# Power.net
KiCad netlist of a schematic drawn in Altium Designer
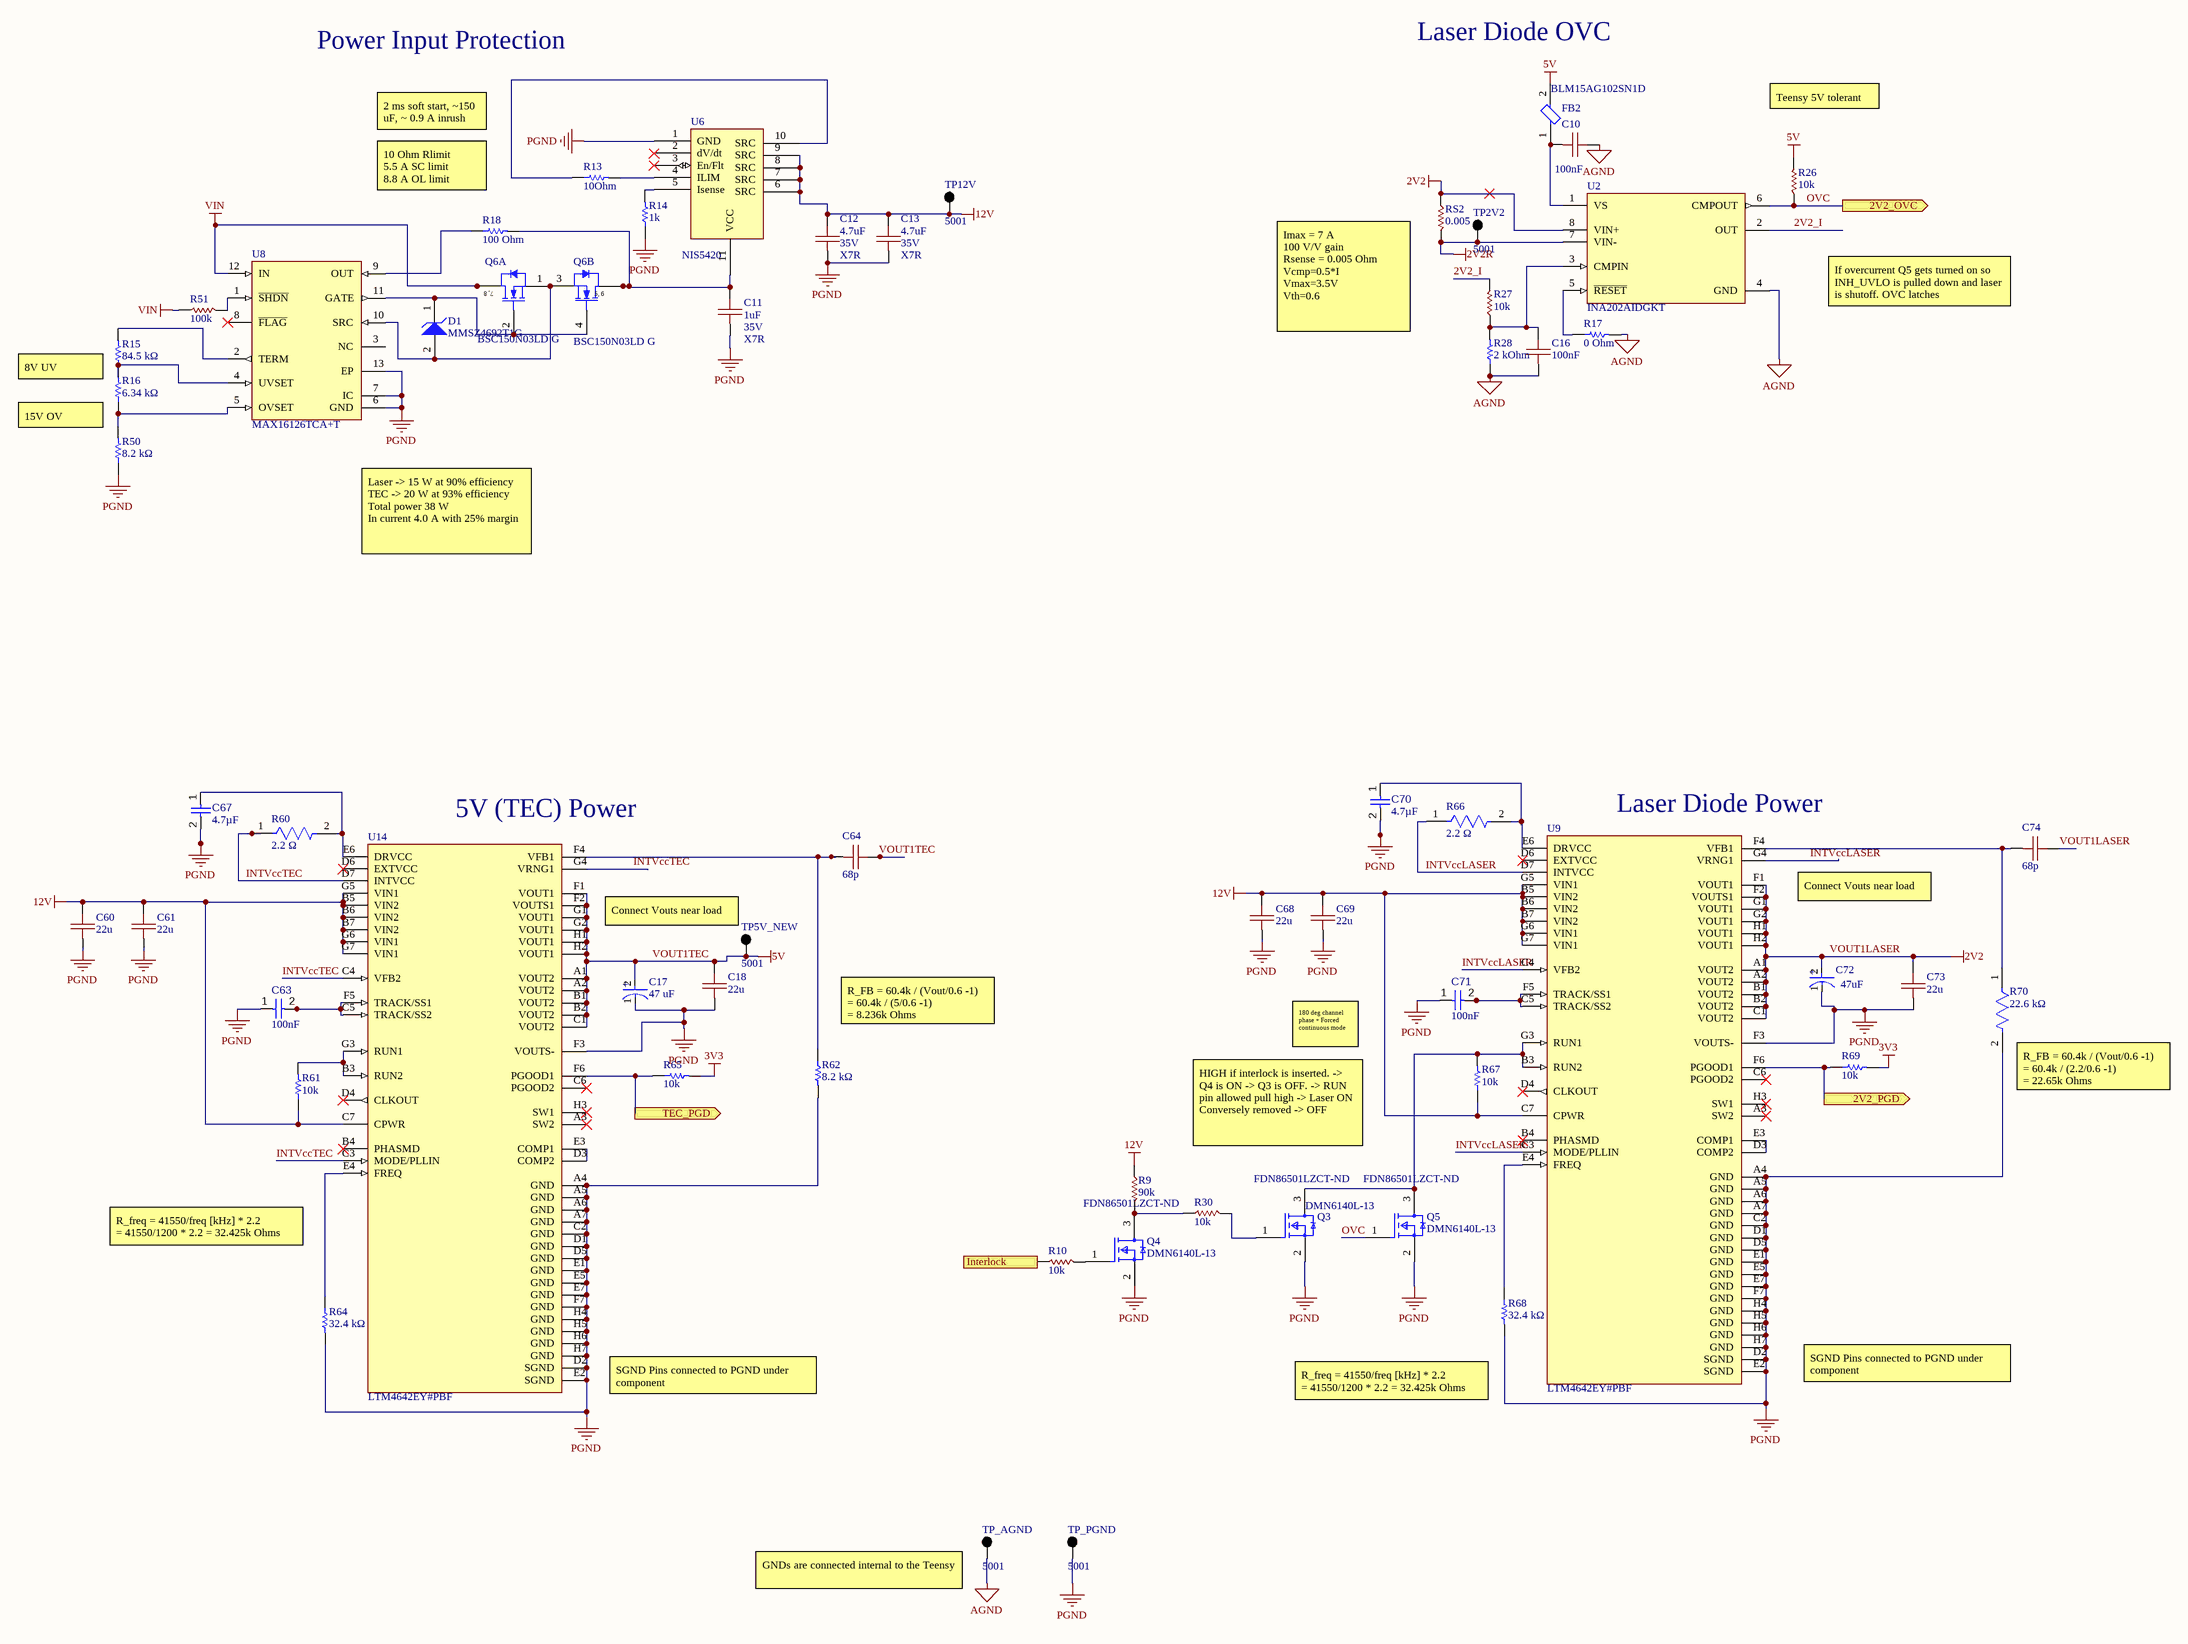
[diagram p0: Power.SchDoc]

(export (version "E")
  (design (tool "Eeschema 10.0.6"))
  (components
    (comp (ref "C10")
      (value "100nF")
      (footprint "0603 B")
      (description "603 Capacitor")
      (libsource (lib "PSSL3") (part "CAP 0603"))
    )
    (comp (ref "C11")
      (value "1uF")
      (footprint "0805 B")
      (description "805 Capacitor")
      (fields (field (name "VOLTAGE") "35V") (field (name "TYPE") "X7R"))
      (libsource (lib "PSSL3") (part "CAP 0805"))
    )
    (comp (ref "C12")
      (value "4.7uF")
      (footprint "0805 B")
      (description "805 Capacitor")
      (fields (field (name "VOLTAGE") "35V") (field (name "TYPE") "X7R"))
      (libsource (lib "PSSL3") (part "CAP 0805"))
    )
    (comp (ref "C13")
      (value "4.7uF")
      (footprint "0805 B")
      (description "805 Capacitor")
      (fields (field (name "VOLTAGE") "35V") (field (name "TYPE") "X7R"))
      (libsource (lib "PSSL3") (part "CAP 0805"))
    )
    (comp (ref "C16")
      (value "100nF")
      (footprint "0603 B")
      (description "603 Capacitor")
      (libsource (lib "PSSL3") (part "CAP 0603"))
    )
    (comp (ref "C17")
      (value "47 uF")
      (footprint "FP-T491D476K025AT-MFG")
      (description "CAP TANT 47UF 10% 25V 2917")
      (fields (field (name "VOLTAGE") "25V") (field (name "TOLERANCE") "10%"))
      (libsource (lib "Altium Content Vault") (part "203bc49f2ac43e59fd269a8c329ed05"))
    )
    (comp (ref "C18")
      (value "22u")
      (footprint "1210")
      (description "1210 Capacitor")
      (libsource (lib "PSSL3") (part "CAP 1210"))
    )
    (comp (ref "C60")
      (value "22u")
      (footprint "1210")
      (description "1210 Capacitor")
      (libsource (lib "PSSL3") (part "CAP 1210"))
    )
    (comp (ref "C61")
      (value "22u")
      (footprint "1210")
      (description "1210 Capacitor")
      (libsource (lib "PSSL3") (part "CAP 1210"))
    )
    (comp (ref "C63")
      (value "100nF")
      (footprint "CAPC1005X56X25LL10T15")
      (description "Chip Capacitor, 0.1 uF, +/- 5%, 16 V, 0402 (1005 Metric)")
      (fields (field (name "TOLERANCE") "5%") (field (name "Comment") "Capacitor 0.1 uF +/- 5% 16 V 0402"))
      (libsource (lib "MIT") (part "CAP-NP-2"))
    )
    (comp (ref "C64")
      (value "68p")
      (footprint "0805 B")
      (description "805 Capacitor")
      (libsource (lib "PSSL3") (part "CAP 0805"))
    )
    (comp (ref "C67")
      (value "4.7µF")
      (footprint "CAPC0805(2012)145_L")
      (description "Chip Capacitor, 4.7µF +/-40%, 25V, 0805, Thickness 1.45 mm")
      (fields (field (name "TOLERANCE") "20%") (field (name "Comment") "Capacitor 4.7µF +/-40% 25V 0805"))
      (libsource (lib "MIT") (part "CAP-NP-2"))
    )
    (comp (ref "C68")
      (value "22u")
      (footprint "1210")
      (description "1210 Capacitor")
      (libsource (lib "PSSL3") (part "CAP 1210"))
    )
    (comp (ref "C69")
      (value "22u")
      (footprint "1210")
      (description "1210 Capacitor")
      (libsource (lib "PSSL3") (part "CAP 1210"))
    )
    (comp (ref "C70")
      (value "4.7µF")
      (footprint "CAPC0805(2012)145_L")
      (description "Chip Capacitor, 4.7µF +/-40%, 25V, 0805, Thickness 1.45 mm")
      (fields (field (name "TOLERANCE") "20%") (field (name "Comment") "Capacitor 4.7µF +/-40% 25V 0805"))
      (libsource (lib "MIT") (part "CAP-NP-2"))
    )
    (comp (ref "C71")
      (value "100nF")
      (footprint "CAPC1005X56X25LL10T15")
      (description "Chip Capacitor, 0.1 uF, +/- 5%, 16 V, 0402 (1005 Metric)")
      (fields (field (name "TOLERANCE") "5%") (field (name "Comment") "Capacitor 0.1 uF +/- 5% 16 V 0402"))
      (libsource (lib "MIT") (part "CAP-NP-2"))
    )
    (comp (ref "C72")
      (value "47 uF")
      (footprint "FP-T491D476K025AT-MFG")
      (description "CAP TANT 47UF 10% 25V 2917")
      (fields
        (field (name "VOLTAGE") "25V")
        (field (name "CAPACITANCE") "47uF")
        (field (name "TOLERANCE") "10%")
      )
      (libsource (lib "Altium Content Vault") (part "203bc49f2ac43e59fd269a8c329ed05"))
    )
    (comp (ref "C73")
      (value "22u")
      (footprint "1210")
      (description "1210 Capacitor")
      (libsource (lib "PSSL3") (part "CAP 1210"))
    )
    (comp (ref "C74")
      (value "68p")
      (footprint "0805 B")
      (description "805 Capacitor")
      (libsource (lib "PSSL3") (part "CAP 0805"))
    )
    (comp (ref "D1")
      (value "MMSZ4692T1G")
      (footprint "ONSC-SOD-123-2-425-04_V")
      (description "Zener Voltage Regulator, 500 mW, 2-Pin SOD-123, Pb-Free, Tape and Reel")
      (fields (field (name "MANUFACTURER") "On Semiconductor"))
      (libsource (lib "Altium Content Vault") (part "ONSC-K1A2-2"))
    )
    (comp (ref "FB2")
      (value "BLM15AG102SN1D")
      (footprint "FP-BLM15-MFG")
      (description "FERRITE BEAD 1 KOHM 0402 1LN")
      (fields
        (field (name "OCTOPART") "https://octopart.com/blm15ag102sn1d-murata-368316")
        (field (name "TOLERANCE") "25%")
      )
      (libsource (lib "Altium Content Vault") (part "5f30dd21d616792df468990f7003faa"))
    )
    (comp (ref "Q3")
      (value "DMN6140L-13")
      (footprint "FP-SOT23-MFG")
      (description "MOSFET N-CH 60V 1.6A SOT23")
      (fields
        (field (name "OCTOPART") "https://octopart.com/dmn6140l-13-diodes+inc.-38898616")
        (field (name "MANUFACTURER") "Diodes Inc.")
        (field (name "SUPPLIER PART NUMBER 2") "FDN86501LZCT-ND")
      )
      (libsource (lib "Altium Content Vault") (part "0a9ea7c96deaaede766a5b531c28de0"))
    )
    (comp (ref "Q4")
      (value "DMN6140L-13")
      (footprint "FP-SOT23-MFG")
      (description "MOSFET N-CH 60V 1.6A SOT23")
      (fields
        (field (name "OCTOPART") "https://octopart.com/dmn6140l-13-diodes+inc.-38898616")
        (field (name "MANUFACTURER") "Diodes Inc.")
        (field (name "SUPPLIER PART NUMBER 2") "FDN86501LZCT-ND")
      )
      (libsource (lib "Altium Content Vault") (part "0a9ea7c96deaaede766a5b531c28de0"))
    )
    (comp (ref "Q5")
      (value "DMN6140L-13")
      (footprint "FP-SOT23-MFG")
      (description "MOSFET N-CH 60V 1.6A SOT23")
      (fields
        (field (name "OCTOPART") "https://octopart.com/dmn6140l-13-diodes+inc.-38898616")
        (field (name "MANUFACTURER") "Diodes Inc.")
        (field (name "SUPPLIER PART NUMBER 2") "FDN86501LZCT-ND")
      )
      (libsource (lib "Altium Content Vault") (part "0a9ea7c96deaaede766a5b531c28de0"))
    )
    (comp (ref "Q6")
      (value "BSC150N03LD G")
      (footprint "INF-PG-TDSON-8-4_V")
      (fields (field (name "MANUFACTURER") "Infineon"))
      (libsource (lib "Altium Content Vault") (part "INF-MOS-BSXXX-8"))
    )
    (comp (ref "R9")
      (value "90k")
      (footprint "0603")
      (description "603 Resistor")
      (libsource (lib "PSSL3") (part "RES 0603"))
    )
    (comp (ref "R10")
      (value "10k")
      (footprint "0603")
      (description "603 Resistor")
      (libsource (lib "PSSL3") (part "RES 0603"))
    )
    (comp (ref "R13")
      (value "10Ohm")
      (footprint "RESC1608X55X25NL10T15")
      (description "Chip Resistor, 10 Ohm, +/- 1%, 0.1 W, -55 to 155 degC, 0603 (1608 Metric), RoHS, Tape and Reel")
      (fields (field (name "MANUFACTURER") "Yageo"))
      (libsource (lib "Altium Content Vault") (part "RES-2"))
    )
    (comp (ref "R14")
      (value "1k")
      (footprint "RESC1608X55X30LL20T20")
      (fields (field (name "MANUFACTURER") "Panasonic") (field (name "PART NUMBER") "ERA3AEB102V"))
      (libsource (lib "Altium Content Vault") (part "RES"))
    )
    (comp (ref "R15")
      (value "84.5 kΩ")
      (footprint "RESC1609X50X30NL10T20")
      (fields (field (name "MANUFACTURER") "Vishay Dale") (field (name "PART NUMBER") "CRCW060384K5FKEA"))
      (libsource (lib "Altium Content Vault") (part "RES"))
    )
    (comp (ref "R16")
      (value "6.34 kΩ")
      (footprint "RESC1608X55X30NL15T15")
      (fields (field (name "PART NUMBER") "ERJ-3EKF6341V") (field (name "MANUFACTURER") "Panasonic"))
      (libsource (lib "Altium Content Vault") (part "RES"))
    )
    (comp (ref "R17")
      (value "0 Ohm")
      (footprint "RESC1608X55X25ML10T15")
      (description "Chip Resistor, 0 Ohm, +/- 5%, 0.1 W, -55 to 155 degC, 0603 (1608 Metric), RoHS, Tape and Reel")
      (fields (field (name "TOLERANCE") "5%") (field (name "MANUFACTURER") "Yageo"))
      (libsource (lib "Altium Content Vault") (part "RES-2"))
    )
    (comp (ref "R18")
      (value "100 Ohm")
      (footprint "RESC1608X55X30LL15T15")
      (fields (field (name "MANUFACTURER") "Panasonic") (field (name "PART NUMBER") "ERJ-3EKF1000V"))
      (libsource (lib "Altium Content Vault") (part "RES"))
    )
    (comp (ref "R26")
      (value "10k")
      (footprint "0603")
      (description "603 Resistor")
      (libsource (lib "PSSL3") (part "RES 0603"))
    )
    (comp (ref "R27")
      (value "10k")
      (footprint "0805")
      (description "805 Resistor")
      (libsource (lib "PSSL3") (part "RES 0805"))
    )
    (comp (ref "R28")
      (value "2 kOhm")
      (footprint "RESC1608X55X30ML15T15")
      (fields (field (name "PART NUMBER") "ERJ-3EKF2001V") (field (name "MANUFACTURER") "Panasonic"))
      (libsource (lib "Altium Content Vault") (part "RES"))
    )
    (comp (ref "R30")
      (value "10k")
      (footprint "0603")
      (description "603 Resistor")
      (libsource (lib "PSSL3") (part "RES 0603"))
    )
    (comp (ref "R50")
      (value "8.2 kΩ")
      (footprint "RESC1609X50X30NL10T20")
      (fields (field (name "PART NUMBER") "CRCW06038K20FKEA") (field (name "MANUFACTURER") "Vishay Dale"))
      (libsource (lib "Altium Content Vault") (part "RES"))
    )
    (comp (ref "R51")
      (value "100k")
      (footprint "0603")
      (description "603 Resistor")
      (libsource (lib "PSSL3") (part "RES 0603"))
    )
    (comp (ref "R60")
      (value "2.2 Ω")
      (footprint "FP-CRCW0603-HPe3-IPC_A")
      (description "RES Thick Film, 2.2Ω, 1%, 0.33W, 100ppm/°C, 0603")
      (fields (field (name "TOLERANCE") "1%"))
      (libsource (lib "Altium Content Vault") (part "1029c3af85768c4190bb7ad29bc67b5"))
    )
    (comp (ref "R61")
      (value "10k")
      (footprint "RESC1608X55X30LL20T20")
      (fields (field (name "MANUFACTURER") "Panasonic") (field (name "PART NUMBER") "ERA3AEB102V"))
      (libsource (lib "Altium Content Vault") (part "RES"))
    )
    (comp (ref "R62")
      (value "8.2 kΩ")
      (footprint "RESC1609X50X30ML10T20")
      (fields (field (name "PART NUMBER") "CRCW06038K20FKEA") (field (name "MANUFACTURER") "Vishay Dale"))
      (libsource (lib "Altium Content Vault") (part "RES"))
    )
    (comp (ref "R64")
      (value "32.4 kΩ")
      (footprint "RESC1609X50X30LL10T20")
      (fields (field (name "MANUFACTURER") "Vishay Dale") (field (name "PART NUMBER") "CRCW060332K4FKEA"))
      (libsource (lib "Altium Content Vault") (part "RES"))
    )
    (comp (ref "R65")
      (value "10k")
      (footprint "RESC1608X55X30LL20T20")
      (fields (field (name "MANUFACTURER") "Panasonic") (field (name "PART NUMBER") "ERA3AEB102V"))
      (libsource (lib "Altium Content Vault") (part "RES"))
    )
    (comp (ref "R66")
      (value "2.2 Ω")
      (footprint "FP-CRCW0603-HPe3-IPC_A")
      (description "RES Thick Film, 2.2Ω, 1%, 0.33W, 100ppm/°C, 0603")
      (fields (field (name "TOLERANCE") "1%"))
      (libsource (lib "Altium Content Vault") (part "1029c3af85768c4190bb7ad29bc67b5"))
    )
    (comp (ref "R67")
      (value "10k")
      (footprint "RESC1608X55X30LL20T20")
      (fields (field (name "MANUFACTURER") "Panasonic") (field (name "PART NUMBER") "ERA3AEB102V"))
      (libsource (lib "Altium Content Vault") (part "RES"))
    )
    (comp (ref "R68")
      (value "32.4 kΩ")
      (footprint "RESC1609X50X30LL10T20")
      (fields (field (name "MANUFACTURER") "Vishay Dale") (field (name "PART NUMBER") "CRCW060332K4FKEA"))
      (libsource (lib "Altium Content Vault") (part "RES"))
    )
    (comp (ref "R69")
      (value "10k")
      (footprint "RESC1608X55X30LL20T20")
      (fields (field (name "MANUFACTURER") "Panasonic") (field (name "PART NUMBER") "ERA3AEB102V"))
      (libsource (lib "Altium Content Vault") (part "RES"))
    )
    (comp (ref "R70")
      (value "22.6 kΩ")
      (footprint "FP-CRCW0402-e3-IPC_C")
      (description "RES Thick Film, 22.6kΩ, 1%, 0.063W, 100ppm/°C, 0402")
      (fields (field (name "TOLERANCE") "1%"))
      (libsource (lib "Altium Content Vault") (part "1029c3af85768c4190bb7ad29bc67b5"))
    )
    (comp (ref "RS2")
      (value "0.005")
      (footprint "1206")
      (description "1206 Resistor")
      (libsource (lib "PSSL3") (part "RES 1206"))
    )
    (comp (ref "TP2V2")
      (value "5001")
      (footprint "KSTN-5001")
      (description "Test Point, Black, 1-Pin THD, RoHS, Bulk")
      (fields (field (name "MANUFACTURER") "Keystone"))
      (libsource (lib "Altium Content Vault") (part "KSTN-TP-5001"))
    )
    (comp (ref "TP5V_NEW")
      (value "5001")
      (footprint "KSTN-5001")
      (description "Test Point, Black, 1-Pin THD, RoHS, Bulk")
      (fields (field (name "MANUFACTURER") "Keystone"))
      (libsource (lib "Altium Content Vault") (part "KSTN-TP-5001"))
    )
    (comp (ref "TP12V")
      (value "5001")
      (footprint "KSTN-5001")
      (description "Test Point, Black, 1-Pin THD, RoHS, Bulk")
      (fields (field (name "MANUFACTURER") "Keystone"))
      (libsource (lib "Altium Content Vault") (part "KSTN-TP-5001"))
    )
    (comp (ref "TP_AGND")
      (value "5001")
      (footprint "KSTN-5001")
      (description "Test Point, Black, 1-Pin THD, RoHS, Bulk")
      (fields (field (name "MANUFACTURER") "Keystone"))
      (libsource (lib "Altium Content Vault") (part "KSTN-TP-5001"))
    )
    (comp (ref "TP_PGND")
      (value "5001")
      (footprint "KSTN-5001")
      (description "Test Point, Black, 1-Pin THD, RoHS, Bulk")
      (fields (field (name "MANUFACTURER") "Keystone"))
      (libsource (lib "Altium Content Vault") (part "KSTN-TP-5001"))
    )
    (comp (ref "U2")
      (value "INA202AIDGKT")
      (footprint "FP-DGK0008A-IPC_A")
      (description "IC CURRENT MONITOR 3.5% 8VSSOP")
      (libsource (lib "Altium Content Vault") (part "ae9e9adbe4fde50626c0decd0408001"))
    )
    (comp (ref "U6")
      (value "NIS5420")
      (footprint "SON50P300X10_HS-11N")
      (libsource (lib "BeaconBoard") (part "NIS5420"))
    )
    (comp (ref "U8")
      (value "MAX16126TCA+T")
      (footprint "T1233+4_N")
      (libsource (lib "Altium Content Vault") (part "MAX-MAX16126-SQ13"))
    )
    (comp (ref "U9")
      (value "LTM4642EY#PBF")
      (footprint "FP-BGA-56-05-08-1961-MFG")
      (description "DC DC CNVRTR 0.6-5.5V 0.6-5.5V")
      (libsource (lib "Altium Content Vault") (part "2369228fab616cff492f64a44cde082"))
    )
    (comp (ref "U14")
      (value "LTM4642EY#PBF")
      (footprint "FP-BGA-56-05-08-1961-MFG")
      (description "DC DC CNVRTR 0.6-5.5V 0.6-5.5V")
      (libsource (lib "Altium Content Vault") (part "2369228fab616cff492f64a44cde082"))
    )
  )
  (nets
    (net (code "1") (name "/2V2_I") (class "Default")
      (node (ref "R27") (pin "1") (pintype "passive"))
      (node (ref "U2") (pin "2") (pinfunction "OUT_2") (pintype "passive"))
    )
    (net (code "2") (name "/2V2_PGD") (class "Default")
      (node (ref "R69") (pin "1") (pinfunction "1_1") (pintype "passive"))
      (node (ref "U9") (pin "F6") (pinfunction "PGOOD1_F6") (pintype "open_collector"))
    )
    (net (code "3") (name "/INTVccLASER") (class "Default")
      (node (ref "R66") (pin "1") (pinfunction "1_1") (pintype "passive"))
      (node (ref "U9") (pin "C3") (pinfunction "MODE/PLLIN_C3") (pintype "input"))
      (node (ref "U9") (pin "C4") (pinfunction "VFB2_C4") (pintype "input"))
      (node (ref "U9") (pin "D7") (pinfunction "INTVCC_D7") (pintype "power_in"))
      (node (ref "U9") (pin "G4") (pinfunction "VRNG1_G4") (pintype "power_in"))
    )
    (net (code "4") (name "/INTVccTEC") (class "Default")
      (node (ref "R60") (pin "1") (pinfunction "1_1") (pintype "passive"))
      (node (ref "U14") (pin "C3") (pinfunction "MODE/PLLIN_C3") (pintype "input"))
      (node (ref "U14") (pin "C4") (pinfunction "VFB2_C4") (pintype "input"))
      (node (ref "U14") (pin "D7") (pinfunction "INTVCC_D7") (pintype "power_in"))
      (node (ref "U14") (pin "G4") (pinfunction "VRNG1_G4") (pintype "power_in"))
    )
    (net (code "5") (name "/Interlock") (class "Default") (node (ref "R10") (pin "2") (pintype "passive")))
    (net (code "6") (name "/OVC") (class "Default")
      (node (ref "Q5") (pin "1") (pinfunction "G_1") (pintype "passive"))
      (node (ref "R26") (pin "2") (pintype "passive"))
      (node (ref "U2") (pin "6") (pinfunction "CMPOUT_6") (pintype "output"))
    )
    (net (code "7") (name "/TEC_PGD") (class "Default")
      (node (ref "R65") (pin "1") (pinfunction "1_1") (pintype "passive"))
      (node (ref "U14") (pin "F6") (pinfunction "PGOOD1_F6") (pintype "open_collector"))
    )
    (net (code "8") (name "2V2") (class "Default")
      (node (ref "C72") (pin "2") (pinfunction "A_2") (pintype "passive"))
      (node (ref "C73") (pin "2") (pintype "passive"))
      (node (ref "C74") (pin "2") (pintype "passive"))
      (node (ref "RS2") (pin "2") (pintype "passive"))
      (node (ref "U2") (pin "8") (pinfunction "VIN+_8") (pintype "tri_state"))
      (node (ref "U9") (pin "A1") (pinfunction "VOUT2_A1") (pintype "passive"))
      (node (ref "U9") (pin "A2") (pinfunction "VOUT2_A2") (pintype "passive"))
      (node (ref "U9") (pin "B1") (pinfunction "VOUT2_B1") (pintype "passive"))
      (node (ref "U9") (pin "B2") (pinfunction "VOUT2_B2") (pintype "passive"))
      (node (ref "U9") (pin "C1") (pinfunction "VOUT2_C1") (pintype "passive"))
      (node (ref "U9") (pin "F1") (pinfunction "VOUT1_F1") (pintype "passive"))
      (node (ref "U9") (pin "F2") (pinfunction "VOUTS1_F2") (pintype "passive"))
      (node (ref "U9") (pin "G1") (pinfunction "VOUT1_G1") (pintype "passive"))
      (node (ref "U9") (pin "G2") (pinfunction "VOUT1_G2") (pintype "passive"))
      (node (ref "U9") (pin "H1") (pinfunction "VOUT1_H1") (pintype "passive"))
      (node (ref "U9") (pin "H2") (pinfunction "VOUT1_H2") (pintype "passive"))
    )
    (net (code "9") (name "2V2R") (class "Default")
      (node (ref "RS2") (pin "1") (pintype "passive"))
      (node (ref "TP2V2") (pin "1") (pintype "passive"))
      (node (ref "U2") (pin "7") (pinfunction "VIN-_7") (pintype "tri_state"))
    )
    (net (code "10") (name "3V3") (class "Default")
      (node (ref "R65") (pin "2") (pinfunction "2_2") (pintype "passive"))
      (node (ref "R69") (pin "2") (pinfunction "2_2") (pintype "passive"))
    )
    (net (code "11") (name "5V") (class "Default")
      (node (ref "C17") (pin "2") (pinfunction "A_2") (pintype "passive"))
      (node (ref "C18") (pin "2") (pintype "passive"))
      (node (ref "C64") (pin "2") (pintype "passive"))
      (node (ref "FB2") (pin "2") (pinfunction "2_2") (pintype "passive"))
      (node (ref "R26") (pin "1") (pintype "passive"))
      (node (ref "TP5V_NEW") (pin "1") (pintype "passive"))
      (node (ref "U14") (pin "A1") (pinfunction "VOUT2_A1") (pintype "passive"))
      (node (ref "U14") (pin "A2") (pinfunction "VOUT2_A2") (pintype "passive"))
      (node (ref "U14") (pin "B1") (pinfunction "VOUT2_B1") (pintype "passive"))
      (node (ref "U14") (pin "B2") (pinfunction "VOUT2_B2") (pintype "passive"))
      (node (ref "U14") (pin "C1") (pinfunction "VOUT2_C1") (pintype "passive"))
      (node (ref "U14") (pin "F1") (pinfunction "VOUT1_F1") (pintype "passive"))
      (node (ref "U14") (pin "F2") (pinfunction "VOUTS1_F2") (pintype "passive"))
      (node (ref "U14") (pin "G1") (pinfunction "VOUT1_G1") (pintype "passive"))
      (node (ref "U14") (pin "G2") (pinfunction "VOUT1_G2") (pintype "passive"))
      (node (ref "U14") (pin "H1") (pinfunction "VOUT1_H1") (pintype "passive"))
      (node (ref "U14") (pin "H2") (pinfunction "VOUT1_H2") (pintype "passive"))
    )
    (net (code "12") (name "12V") (class "Default")
      (node (ref "C12") (pin "2") (pintype "passive"))
      (node (ref "C13") (pin "2") (pintype "passive"))
      (node (ref "C60") (pin "2") (pintype "passive"))
      (node (ref "C61") (pin "2") (pintype "passive"))
      (node (ref "C68") (pin "2") (pintype "passive"))
      (node (ref "C69") (pin "2") (pintype "passive"))
      (node (ref "R61") (pin "1") (pinfunction "1_1") (pintype "passive"))
      (node (ref "R67") (pin "1") (pinfunction "1_1") (pintype "passive"))
      (node (ref "R9") (pin "2") (pintype "passive"))
      (node (ref "TP12V") (pin "1") (pintype "passive"))
      (node (ref "U14") (pin "B5") (pinfunction "VIN2_B5") (pintype "power_in"))
      (node (ref "U14") (pin "B6") (pinfunction "VIN2_B6") (pintype "power_in"))
      (node (ref "U14") (pin "B7") (pinfunction "VIN2_B7") (pintype "power_in"))
      (node (ref "U14") (pin "C7") (pinfunction "CPWR_C7") (pintype "passive"))
      (node (ref "U14") (pin "G5") (pinfunction "VIN1_G5") (pintype "power_in"))
      (node (ref "U14") (pin "G6") (pinfunction "VIN1_G6") (pintype "power_in"))
      (node (ref "U14") (pin "G7") (pinfunction "VIN1_G7") (pintype "power_in"))
      (node (ref "U6") (pin "6") (pinfunction "SRC_6") (pintype "power_in"))
      (node (ref "U6") (pin "7") (pinfunction "SRC_7") (pintype "power_in"))
      (node (ref "U6") (pin "8") (pinfunction "SRC_8") (pintype "power_in"))
      (node (ref "U6") (pin "9") (pinfunction "SRC_9") (pintype "power_in"))
      (node (ref "U9") (pin "B5") (pinfunction "VIN2_B5") (pintype "power_in"))
      (node (ref "U9") (pin "B6") (pinfunction "VIN2_B6") (pintype "power_in"))
      (node (ref "U9") (pin "B7") (pinfunction "VIN2_B7") (pintype "power_in"))
      (node (ref "U9") (pin "C7") (pinfunction "CPWR_C7") (pintype "passive"))
      (node (ref "U9") (pin "G5") (pinfunction "VIN1_G5") (pintype "power_in"))
      (node (ref "U9") (pin "G6") (pinfunction "VIN1_G6") (pintype "power_in"))
      (node (ref "U9") (pin "G7") (pinfunction "VIN1_G7") (pintype "power_in"))
    )
    (net (code "13") (name "AGND") (class "Default")
      (node (ref "C10") (pin "2") (pintype "passive"))
      (node (ref "C16") (pin "1") (pintype "passive"))
      (node (ref "R17") (pin "2") (pinfunction "2_2") (pintype "passive"))
      (node (ref "R28") (pin "1") (pinfunction "1_1") (pintype "passive"))
      (node (ref "TP_AGND") (pin "1") (pintype "passive"))
      (node (ref "U2") (pin "4") (pinfunction "GND_4") (pintype "power_in"))
    )
    (net (code "14") (name "Net-(D1-A)") (class "Default")
      (node (ref "D1") (pin "2") (pinfunction "A_2") (pintype "passive"))
      (node (ref "Q6") (pin "1") (pinfunction "S1_1") (pintype "passive"))
      (node (ref "Q6") (pin "3") (pinfunction "S2_3") (pintype "passive"))
      (node (ref "U8") (pin "10") (pinfunction "SRC_10") (pintype "input"))
    )
    (net (code "15") (name "Net-(D1-K)") (class "Default")
      (node (ref "D1") (pin "1") (pinfunction "K_1") (pintype "passive"))
      (node (ref "Q6") (pin "2") (pinfunction "G1_2") (pintype "passive"))
      (node (ref "Q6") (pin "4") (pinfunction "G2_4") (pintype "passive"))
      (node (ref "U8") (pin "11") (pinfunction "GATE_11") (pintype "output"))
    )
    (net (code "16") (name "Net-(Q3-D)") (class "Default")
      (node (ref "Q3") (pin "3") (pinfunction "D_3") (pintype "passive"))
      (node (ref "Q5") (pin "3") (pinfunction "D_3") (pintype "passive"))
      (node (ref "R67") (pin "2") (pinfunction "2_2") (pintype "passive"))
      (node (ref "U9") (pin "B3") (pinfunction "RUN2_B3") (pintype "input"))
      (node (ref "U9") (pin "G3") (pinfunction "RUN1_G3") (pintype "input"))
    )
    (net (code "17") (name "Net-(Q3-G)") (class "Default")
      (node (ref "Q3") (pin "1") (pinfunction "G_1") (pintype "passive"))
      (node (ref "R30") (pin "1") (pintype "passive"))
    )
    (net (code "18") (name "Net-(Q4-D)") (class "Default")
      (node (ref "Q4") (pin "3") (pinfunction "D_3") (pintype "passive"))
      (node (ref "R30") (pin "2") (pintype "passive"))
      (node (ref "R9") (pin "1") (pintype "passive"))
    )
    (net (code "19") (name "Net-(Q4-G)") (class "Default")
      (node (ref "Q4") (pin "1") (pinfunction "G_1") (pintype "passive"))
      (node (ref "R10") (pin "1") (pintype "passive"))
    )
    (net (code "20") (name "Net-(R13-Pad1)") (class "Default")
      (node (ref "R13") (pin "1") (pinfunction "1_1") (pintype "passive"))
      (node (ref "U6") (pin "10") (pinfunction "SRC_10") (pintype "power_in"))
    )
    (net (code "21") (name "Net-(U2-CMPIN)") (class "Default")
      (node (ref "C16") (pin "2") (pintype "passive"))
      (node (ref "R27") (pin "2") (pintype "passive"))
      (node (ref "R28") (pin "2") (pinfunction "2_2") (pintype "passive"))
      (node (ref "U2") (pin "3") (pinfunction "CMPIN_3") (pintype "input"))
    )
    (net (code "22") (name "Net-(U2-VS)") (class "Default")
      (node (ref "C10") (pin "1") (pintype "passive"))
      (node (ref "FB2") (pin "1") (pinfunction "1_1") (pintype "passive"))
      (node (ref "U2") (pin "1") (pinfunction "VS_1") (pintype "power_in"))
    )
    (net (code "23") (name "Net-(U2-~{RESET})") (class "Default")
      (node (ref "R17") (pin "1") (pinfunction "1_1") (pintype "passive"))
      (node (ref "U2") (pin "5") (pinfunction "~{RESET}_5") (pintype "input"))
    )
    (net (code "24") (name "Net-(U6-ILIM)") (class "Default")
      (node (ref "R13") (pin "2") (pinfunction "2_2") (pintype "passive"))
      (node (ref "U6") (pin "4") (pinfunction "ILIM_4") (pintype "passive"))
    )
    (net (code "25") (name "Net-(U6-Isense)") (class "Default")
      (node (ref "R14") (pin "2") (pinfunction "2_2") (pintype "passive"))
      (node (ref "U6") (pin "5") (pinfunction "Isense_5") (pintype "passive"))
    )
    (net (code "26") (name "Net-(U6-VCC)") (class "Default")
      (node (ref "C11") (pin "2") (pintype "passive"))
      (node (ref "Q6") (pin "5") (pinfunction "D2_5") (pintype "passive"))
      (node (ref "Q6") (pin "6") (pinfunction "D2_6") (pintype "passive"))
      (node (ref "R18") (pin "2") (pinfunction "2_2") (pintype "passive"))
      (node (ref "U6") (pin "11") (pinfunction "VCC_11") (pintype "power_in"))
    )
    (net (code "27") (name "Net-(U8-OUT)") (class "Default")
      (node (ref "R18") (pin "1") (pinfunction "1_1") (pintype "passive"))
      (node (ref "U8") (pin "9") (pinfunction "OUT_9") (pintype "input"))
    )
    (net (code "28") (name "Net-(U8-OVSET)") (class "Default")
      (node (ref "R16") (pin "1") (pinfunction "1_1") (pintype "passive"))
      (node (ref "R50") (pin "2") (pinfunction "2_2") (pintype "passive"))
      (node (ref "U8") (pin "5") (pinfunction "OVSET_5") (pintype "input"))
    )
    (net (code "29") (name "Net-(U8-TERM)") (class "Default")
      (node (ref "R15") (pin "2") (pinfunction "2_2") (pintype "passive"))
      (node (ref "U8") (pin "2") (pinfunction "TERM_2") (pintype "output"))
    )
    (net (code "30") (name "Net-(U8-UVSET)") (class "Default")
      (node (ref "R15") (pin "1") (pinfunction "1_1") (pintype "passive"))
      (node (ref "R16") (pin "2") (pinfunction "2_2") (pintype "passive"))
      (node (ref "U8") (pin "4") (pinfunction "UVSET_4") (pintype "input"))
    )
    (net (code "31") (name "Net-(U8-~{SHDN})") (class "Default")
      (node (ref "R51") (pin "1") (pintype "passive"))
      (node (ref "U8") (pin "1") (pinfunction "~{SHDN}_1") (pintype "input"))
    )
    (net (code "32") (name "Net-(U9-COMP1)") (class "Default")
      (node (ref "U9") (pin "D3") (pinfunction "COMP2_D3") (pintype "passive"))
      (node (ref "U9") (pin "E3") (pinfunction "COMP1_E3") (pintype "passive"))
    )
    (net (code "33") (name "Net-(U9-DRVCC)") (class "Default")
      (node (ref "C70") (pin "1") (pinfunction "1_1") (pintype "passive"))
      (node (ref "R66") (pin "2") (pinfunction "2_2") (pintype "passive"))
      (node (ref "U9") (pin "E6") (pinfunction "DRVCC_E6") (pintype "power_in"))
    )
    (net (code "34") (name "Net-(U9-FREQ)") (class "Default")
      (node (ref "R68") (pin "1") (pinfunction "1_1") (pintype "passive"))
      (node (ref "U9") (pin "E4") (pinfunction "FREQ_E4") (pintype "input"))
    )
    (net (code "35") (name "Net-(U9-TRACK{slash}SS1)") (class "Default")
      (node (ref "C71") (pin "2") (pinfunction "2_2") (pintype "passive"))
      (node (ref "U9") (pin "C5") (pinfunction "TRACK/SS2_C5") (pintype "input"))
      (node (ref "U9") (pin "F5") (pinfunction "TRACK/SS1_F5") (pintype "input"))
    )
    (net (code "36") (name "Net-(U9-VFB1)") (class "Default")
      (node (ref "C74") (pin "1") (pintype "passive"))
      (node (ref "R70") (pin "1") (pinfunction "1_1") (pintype "passive"))
      (node (ref "U9") (pin "F4") (pinfunction "VFB1_F4") (pintype "passive"))
    )
    (net (code "37") (name "Net-(U14-COMP1)") (class "Default")
      (node (ref "U14") (pin "D3") (pinfunction "COMP2_D3") (pintype "passive"))
      (node (ref "U14") (pin "E3") (pinfunction "COMP1_E3") (pintype "passive"))
    )
    (net (code "38") (name "Net-(U14-DRVCC)") (class "Default")
      (node (ref "C67") (pin "1") (pinfunction "1_1") (pintype "passive"))
      (node (ref "R60") (pin "2") (pinfunction "2_2") (pintype "passive"))
      (node (ref "U14") (pin "E6") (pinfunction "DRVCC_E6") (pintype "power_in"))
    )
    (net (code "39") (name "Net-(U14-FREQ)") (class "Default")
      (node (ref "R64") (pin "1") (pinfunction "1_1") (pintype "passive"))
      (node (ref "U14") (pin "E4") (pinfunction "FREQ_E4") (pintype "input"))
    )
    (net (code "40") (name "Net-(U14-RUN1)") (class "Default")
      (node (ref "R61") (pin "2") (pinfunction "2_2") (pintype "passive"))
      (node (ref "U14") (pin "B3") (pinfunction "RUN2_B3") (pintype "input"))
      (node (ref "U14") (pin "G3") (pinfunction "RUN1_G3") (pintype "input"))
    )
    (net (code "41") (name "Net-(U14-TRACK{slash}SS1)") (class "Default")
      (node (ref "C63") (pin "2") (pinfunction "2_2") (pintype "passive"))
      (node (ref "U14") (pin "C5") (pinfunction "TRACK/SS2_C5") (pintype "input"))
      (node (ref "U14") (pin "F5") (pinfunction "TRACK/SS1_F5") (pintype "input"))
    )
    (net (code "42") (name "Net-(U14-VFB1)") (class "Default")
      (node (ref "C64") (pin "1") (pintype "passive"))
      (node (ref "R62") (pin "1") (pinfunction "1_1") (pintype "passive"))
      (node (ref "U14") (pin "F4") (pinfunction "VFB1_F4") (pintype "passive"))
    )
    (net (code "43") (name "PGND") (class "Default")
      (node (ref "C11") (pin "1") (pintype "passive"))
      (node (ref "C12") (pin "1") (pintype "passive"))
      (node (ref "C13") (pin "1") (pintype "passive"))
      (node (ref "C17") (pin "1") (pinfunction "C_1") (pintype "passive"))
      (node (ref "C18") (pin "1") (pintype "passive"))
      (node (ref "C60") (pin "1") (pintype "passive"))
      (node (ref "C61") (pin "1") (pintype "passive"))
      (node (ref "C63") (pin "1") (pinfunction "1_1") (pintype "passive"))
      (node (ref "C67") (pin "2") (pinfunction "2_2") (pintype "passive"))
      (node (ref "C68") (pin "1") (pintype "passive"))
      (node (ref "C69") (pin "1") (pintype "passive"))
      (node (ref "C70") (pin "2") (pinfunction "2_2") (pintype "passive"))
      (node (ref "C71") (pin "1") (pinfunction "1_1") (pintype "passive"))
      (node (ref "C72") (pin "1") (pinfunction "C_1") (pintype "passive"))
      (node (ref "C73") (pin "1") (pintype "passive"))
      (node (ref "Q3") (pin "2") (pinfunction "S_2") (pintype "passive"))
      (node (ref "Q4") (pin "2") (pinfunction "S_2") (pintype "passive"))
      (node (ref "Q5") (pin "2") (pinfunction "S_2") (pintype "passive"))
      (node (ref "R14") (pin "1") (pinfunction "1_1") (pintype "passive"))
      (node (ref "R50") (pin "1") (pinfunction "1_1") (pintype "passive"))
      (node (ref "R62") (pin "2") (pinfunction "2_2") (pintype "passive"))
      (node (ref "R64") (pin "2") (pinfunction "2_2") (pintype "passive"))
      (node (ref "R68") (pin "2") (pinfunction "2_2") (pintype "passive"))
      (node (ref "R70") (pin "2") (pinfunction "2_2") (pintype "passive"))
      (node (ref "TP_PGND") (pin "1") (pintype "passive"))
      (node (ref "U14") (pin "A4") (pinfunction "GND_A4") (pintype "power_in"))
      (node (ref "U14") (pin "A5") (pinfunction "GND_A5") (pintype "power_in"))
      (node (ref "U14") (pin "A6") (pinfunction "GND_A6") (pintype "power_in"))
      (node (ref "U14") (pin "A7") (pinfunction "GND_A7") (pintype "power_in"))
      (node (ref "U14") (pin "C2") (pinfunction "GND_C2") (pintype "power_in"))
      (node (ref "U14") (pin "D1") (pinfunction "GND_D1") (pintype "power_in"))
      (node (ref "U14") (pin "D2") (pinfunction "SGND_D2") (pintype "power_in"))
      (node (ref "U14") (pin "D5") (pinfunction "GND_D5") (pintype "power_in"))
      (node (ref "U14") (pin "E1") (pinfunction "GND_E1") (pintype "power_in"))
      (node (ref "U14") (pin "E2") (pinfunction "SGND_E2") (pintype "power_in"))
      (node (ref "U14") (pin "E5") (pinfunction "GND_E5") (pintype "power_in"))
      (node (ref "U14") (pin "E7") (pinfunction "GND_E7") (pintype "power_in"))
      (node (ref "U14") (pin "F3") (pinfunction "VOUTS-_F3") (pintype "passive"))
      (node (ref "U14") (pin "F7") (pinfunction "GND_F7") (pintype "power_in"))
      (node (ref "U14") (pin "H4") (pinfunction "GND_H4") (pintype "power_in"))
      (node (ref "U14") (pin "H5") (pinfunction "GND_H5") (pintype "power_in"))
      (node (ref "U14") (pin "H6") (pinfunction "GND_H6") (pintype "power_in"))
      (node (ref "U14") (pin "H7") (pinfunction "GND_H7") (pintype "power_in"))
      (node (ref "U6") (pin "1") (pinfunction "GND_1") (pintype "power_in"))
      (node (ref "U8") (pin "13") (pinfunction "EP_13") (pintype "passive"))
      (node (ref "U8") (pin "6") (pinfunction "GND_6") (pintype "power_in"))
      (node (ref "U8") (pin "7") (pinfunction "IC_7") (pintype "power_in"))
      (node (ref "U9") (pin "A4") (pinfunction "GND_A4") (pintype "power_in"))
      (node (ref "U9") (pin "A5") (pinfunction "GND_A5") (pintype "power_in"))
      (node (ref "U9") (pin "A6") (pinfunction "GND_A6") (pintype "power_in"))
      (node (ref "U9") (pin "A7") (pinfunction "GND_A7") (pintype "power_in"))
      (node (ref "U9") (pin "C2") (pinfunction "GND_C2") (pintype "power_in"))
      (node (ref "U9") (pin "D1") (pinfunction "GND_D1") (pintype "power_in"))
      (node (ref "U9") (pin "D2") (pinfunction "SGND_D2") (pintype "power_in"))
      (node (ref "U9") (pin "D5") (pinfunction "GND_D5") (pintype "power_in"))
      (node (ref "U9") (pin "E1") (pinfunction "GND_E1") (pintype "power_in"))
      (node (ref "U9") (pin "E2") (pinfunction "SGND_E2") (pintype "power_in"))
      (node (ref "U9") (pin "E5") (pinfunction "GND_E5") (pintype "power_in"))
      (node (ref "U9") (pin "E7") (pinfunction "GND_E7") (pintype "power_in"))
      (node (ref "U9") (pin "F3") (pinfunction "VOUTS-_F3") (pintype "passive"))
      (node (ref "U9") (pin "F7") (pinfunction "GND_F7") (pintype "power_in"))
      (node (ref "U9") (pin "H4") (pinfunction "GND_H4") (pintype "power_in"))
      (node (ref "U9") (pin "H5") (pinfunction "GND_H5") (pintype "power_in"))
      (node (ref "U9") (pin "H6") (pinfunction "GND_H6") (pintype "power_in"))
      (node (ref "U9") (pin "H7") (pinfunction "GND_H7") (pintype "power_in"))
    )
    (net (code "44") (name "VIN") (class "Default")
      (node (ref "Q6") (pin "7") (pinfunction "D1_7") (pintype "passive"))
      (node (ref "Q6") (pin "8") (pinfunction "D1_8") (pintype "passive"))
      (node (ref "R51") (pin "2") (pintype "passive"))
      (node (ref "U8") (pin "12") (pinfunction "IN_12") (pintype "input"))
    )
    (net (code "45") (name "unconnected-(U6-En{slash}Flt-Pad3)") (class "Default")
      (node (ref "U6") (pin "3") (pinfunction "En/Flt_3") (pintype "bidirectional+no_connect"))
    )
    (net (code "46") (name "unconnected-(U6-dV{slash}dt-Pad2)") (class "Default")
      (node (ref "U6") (pin "2") (pinfunction "dV/dt_2") (pintype "passive+no_connect"))
    )
    (net (code "47") (name "unconnected-(U8-NC-Pad3)") (class "Default")
      (node (ref "U8") (pin "3") (pinfunction "NC_3") (pintype "passive"))
    )
    (net (code "48") (name "unconnected-(U8-~{FLAG}-Pad8)") (class "Default")
      (node (ref "U8") (pin "8") (pinfunction "~{FLAG}_8") (pintype "open_collector+no_connect"))
    )
    (net (code "49") (name "unconnected-(U9-CLKOUT-PadD4)") (class "Default")
      (node (ref "U9") (pin "D4") (pinfunction "CLKOUT_D4") (pintype "output+no_connect"))
    )
    (net (code "50") (name "unconnected-(U9-EXTVCC-PadD6)") (class "Default")
      (node (ref "U9") (pin "D6") (pinfunction "EXTVCC_D6") (pintype "power_in+no_connect"))
    )
    (net (code "51") (name "unconnected-(U9-PGOOD2-PadC6)") (class "Default")
      (node (ref "U9") (pin "C6") (pinfunction "PGOOD2_C6") (pintype "open_collector+no_connect"))
    )
    (net (code "52") (name "unconnected-(U9-PHASMD-PadB4)") (class "Default")
      (node (ref "U9") (pin "B4") (pinfunction "PHASMD_B4") (pintype "passive+no_connect"))
    )
    (net (code "53") (name "unconnected-(U9-SW1-PadH3)") (class "Default")
      (node (ref "U9") (pin "H3") (pinfunction "SW1_H3") (pintype "passive+no_connect"))
    )
    (net (code "54") (name "unconnected-(U9-SW2-PadA3)") (class "Default")
      (node (ref "U9") (pin "A3") (pinfunction "SW2_A3") (pintype "passive+no_connect"))
    )
    (net (code "55") (name "unconnected-(U14-CLKOUT-PadD4)") (class "Default")
      (node (ref "U14") (pin "D4") (pinfunction "CLKOUT_D4") (pintype "output+no_connect"))
    )
    (net (code "56") (name "unconnected-(U14-EXTVCC-PadD6)") (class "Default")
      (node (ref "U14") (pin "D6") (pinfunction "EXTVCC_D6") (pintype "power_in+no_connect"))
    )
    (net (code "57") (name "unconnected-(U14-PGOOD2-PadC6)") (class "Default")
      (node (ref "U14") (pin "C6") (pinfunction "PGOOD2_C6") (pintype "open_collector+no_connect"))
    )
    (net (code "58") (name "unconnected-(U14-PHASMD-PadB4)") (class "Default")
      (node (ref "U14") (pin "B4") (pinfunction "PHASMD_B4") (pintype "passive+no_connect"))
    )
    (net (code "59") (name "unconnected-(U14-SW1-PadH3)") (class "Default")
      (node (ref "U14") (pin "H3") (pinfunction "SW1_H3") (pintype "passive+no_connect"))
    )
    (net (code "60") (name "unconnected-(U14-SW2-PadA3)") (class "Default")
      (node (ref "U14") (pin "A3") (pinfunction "SW2_A3") (pintype "passive+no_connect"))
    )
  )
)
